# MB1296-LRA_Module.net
KiCad netlist of a schematic drawn in Altium Designer
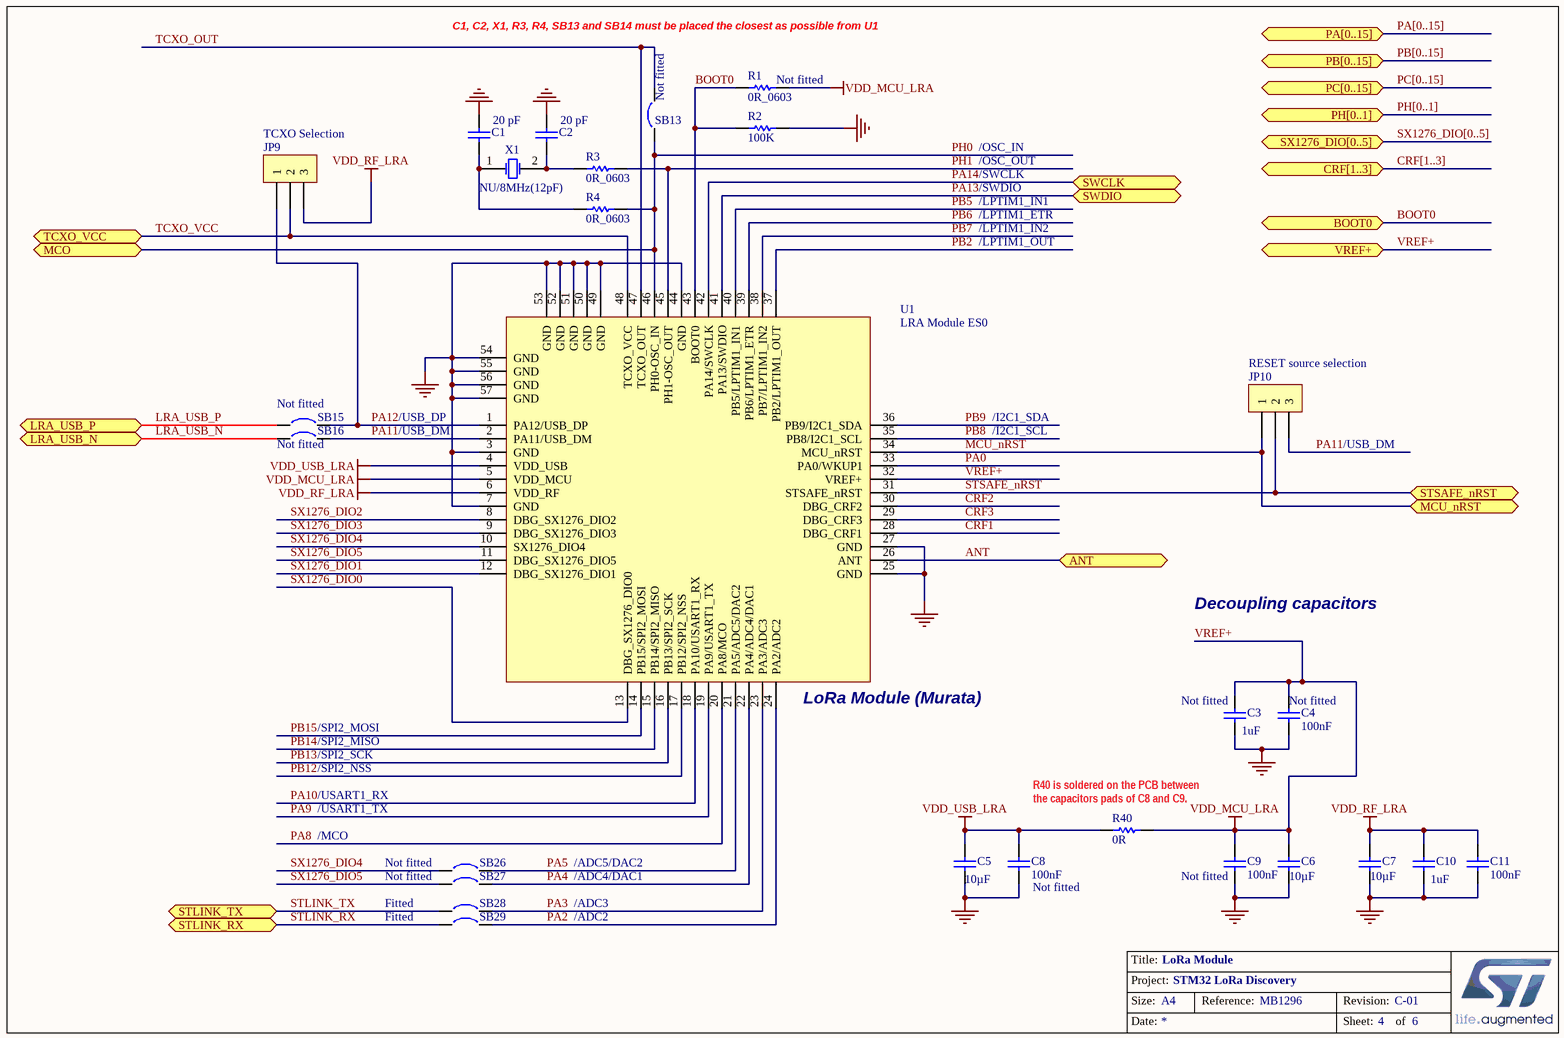
[diagram p0: MB1296-LRA_Module.SchDoc]

(export (version "E")
  (design (tool "Eeschema 10.0.6"))
  (components
    (comp (ref "C1")
      (value "20 pF")
      (footprint "0603C")
      (description "Capacitor 0603")
      (fields (field (name "MANUFACTURER") "YAGEO") (field (name "PROVIDED BY") "Subcon"))
      (libsource (lib "MCD16-033-STM32_LRA_Eval_Board_1") (part "Capacitor_ST"))
    )
    (comp (ref "C2")
      (value "20 pF")
      (footprint "0603C")
      (description "Capacitor 0603")
      (fields (field (name "MANUFACTURER") "YAGEO") (field (name "PROVIDED BY") "Subcon"))
      (libsource (lib "MCD16-033-STM32_LRA_Eval_Board_1") (part "Capacitor_ST"))
    )
    (comp (ref "C3")
      (value "1uF")
      (footprint "0603C")
      (description "0603  X5R 1µF")
      (fields (field (name "MANUFACTURER") "YAGEO") (field (name "PROVIDED BY") "Subcon"))
      (libsource (lib "MCD16-033-STM32_LRA_Eval_Board_1") (part "CAP SMD 0603  X5R 1µF 25V 10%"))
    )
    (comp (ref "C4")
      (value "100nF")
      (footprint "0603C")
      (description "Capacitor 100nF")
      (fields (field (name "MANUFACTURER") "YAGEO") (field (name "PROVIDED BY") "Subcon"))
      (libsource (lib "MCD16-033-STM32_LRA_Eval_Board_1") (part "CAP"))
    )
    (comp (ref "C5")
      (value "10µF")
      (footprint "0603C")
      (description "Capacitor SMD 0805 10000000pF X7R 10V +/-10%")
      (fields (field (name "MANUFACTURER") "Kemet") (field (name "TOLERANCE") "10%"))
      (libsource (lib "Capacitor_0805") (part "CAP_C0805C106K8RACTU"))
    )
    (comp (ref "C6")
      (value "10µF")
      (footprint "0603C")
      (description "Capacitor SMD 0805 10000000pF X7R 10V +/-10%")
      (fields (field (name "MANUFACTURER") "Kemet") (field (name "TOLERANCE") "10%"))
      (libsource (lib "Capacitor_0805") (part "CAP_C0805C106K8RACTU"))
    )
    (comp (ref "C7")
      (value "10µF")
      (footprint "0603C")
      (description "Capacitor SMD 0805 10000000pF X7R 10V +/-10%")
      (fields (field (name "MANUFACTURER") "Kemet") (field (name "TOLERANCE") "10%"))
      (libsource (lib "Capacitor_0805") (part "CAP_C0805C106K8RACTU"))
    )
    (comp (ref "C8")
      (value "100nF")
      (footprint "0603C")
      (description "Capacitor 100nF")
      (fields (field (name "MANUFACTURER") "YAGEO") (field (name "PROVIDED BY") "Subcon"))
      (libsource (lib "MCD16-033-STM32_LRA_Eval_Board_1") (part "CAP"))
    )
    (comp (ref "C9")
      (value "100nF")
      (footprint "0603C")
      (description "Capacitor 100nF")
      (fields (field (name "MANUFACTURER") "YAGEO") (field (name "PROVIDED BY") "Subcon"))
      (libsource (lib "MCD16-033-STM32_LRA_Eval_Board_1") (part "CAP"))
    )
    (comp (ref "C10")
      (value "1uF")
      (footprint "0603C")
      (description "0603  X5R 1µF")
      (fields (field (name "MANUFACTURER") "YAGEO") (field (name "PROVIDED BY") "Subcon"))
      (libsource (lib "MCD16-033-STM32_LRA_Eval_Board_1") (part "CAP SMD 0603  X5R 1µF 25V 10%"))
    )
    (comp (ref "C11")
      (value "100nF")
      (footprint "0603C")
      (description "Capacitor 100nF")
      (fields (field (name "MANUFACTURER") "YAGEO") (field (name "PROVIDED BY") "Subcon"))
      (libsource (lib "MCD16-033-STM32_LRA_Eval_Board_1") (part "CAP"))
    )
    (comp (ref "JP9")
      (value "TCXO Selection")
      (footprint "SIP3")
      (description "Header 3")
      (fields (field (name "MANUFACTURER") "Kontek") (field (name "PROVIDED BY") "Subcon"))
      (libsource (lib "MCD16-033-STM32_LRA_Eval_Board_1") (part "Header 3"))
    )
    (comp (ref "JP10")
      (value "RESET source selection")
      (footprint "SIP3")
      (description "Header 3")
      (fields (field (name "MANUFACTURER") "Kontek") (field (name "PROVIDED BY") "Subcon"))
      (libsource (lib "MCD16-033-STM32_LRA_Eval_Board_1") (part "Header 3"))
    )
    (comp (ref "R1")
      (value "0R_0603")
      (footprint "0603")
      (description "0603 0R 50V 0.1W")
      (fields (field (name "MANUFACTURER") "YAGEO"))
      (libsource (lib "Resistor_0603") (part "RES SMD 0603 0R 50V 0.1W"))
    )
    (comp (ref "R2")
      (value "100K")
      (footprint "0603")
      (description "0603 100K 75V 5% 0.1W")
      (fields (field (name "MANUFACTURER") "YAGEO") (field (name "PROVIDED BY") "Subcon"))
      (libsource (lib "MCD16-033-STM32_LRA_Eval_Board_1") (part "RES SMD 0603 100K 75V 5% 0.1W"))
    )
    (comp (ref "R3")
      (value "0R_0603")
      (footprint "0603")
      (description "0603 0R 50V 0.1W")
      (fields (field (name "MANUFACTURER") "YAGEO"))
      (libsource (lib "Resistor_0603") (part "RES SMD 0603 0R 50V 0.1W"))
    )
    (comp (ref "R4")
      (value "0R_0603")
      (footprint "0603")
      (description "0603 0R 50V 0.1W")
      (fields (field (name "MANUFACTURER") "YAGEO"))
      (libsource (lib "Resistor_0603") (part "RES SMD 0603 0R 50V 0.1W"))
    )
    (comp (ref "R40")
      (value "0R")
      (footprint "0603")
      (description "0603 100K 75V 5% 0.1W")
      (fields (field (name "MANUFACTURER") "YAGEO") (field (name "PROVIDED BY") "Subcon"))
      (libsource (lib "MCD16-033-STM32_LRA_Eval_Board_1") (part "RES SMD 0603 100K 75V 5% 0.1W"))
    )
    (comp (ref "SB13")
      (value "Circuit Breaker")
      (footprint "JP2_SMD")
      (libsource (lib "MCD16-033-STM32_LRA_Eval_Board_1") (part "Circuit Breaker"))
    )
    (comp (ref "SB15")
      (value "Circuit Breaker")
      (footprint "JP2_SMD")
      (libsource (lib "MCD16-033-STM32_LRA_Eval_Board_1") (part "Circuit Breaker"))
    )
    (comp (ref "SB16")
      (value "Circuit Breaker")
      (footprint "JP2_SMD")
      (libsource (lib "MCD16-033-STM32_LRA_Eval_Board_1") (part "Circuit Breaker"))
    )
    (comp (ref "SB26")
      (value "Circuit Breaker")
      (footprint "JP2_SMD")
      (libsource (lib "MCD16-033-STM32_LRA_Eval_Board_1") (part "Circuit Breaker"))
    )
    (comp (ref "SB27")
      (value "Circuit Breaker")
      (footprint "JP2_SMD")
      (libsource (lib "MCD16-033-STM32_LRA_Eval_Board_1") (part "Circuit Breaker"))
    )
    (comp (ref "SB28")
      (value "Circuit Breaker")
      (footprint "JP2_SMD")
      (libsource (lib "MCD16-033-STM32_LRA_Eval_Board_1") (part "Circuit Breaker"))
    )
    (comp (ref "SB29")
      (value "Circuit Breaker")
      (footprint "JP2_SMD")
      (libsource (lib "MCD16-033-STM32_LRA_Eval_Board_1") (part "Circuit Breaker"))
    )
    (comp (ref "U1")
      (value "LRA Module ES0")
      (footprint "Lora Module ES0")
      (fields (field (name "MANUFACTURER") "Murata") (field (name "PROVIDED BY") "Murata"))
      (libsource (lib "Integrated_Circuit") (part "LRA Module ES0"))
    )
    (comp (ref "X1")
      (value "NU/8MHz(12pF)")
      (footprint "CRY_NX3225GD_2P")
      (description "Crystal Oscillator")
      (fields (field (name "MANUFACTURER") "HongKongCrystal") (field (name "PROVIDED BY") "Subcon"))
      (libsource (lib "MB963_1") (part "XTAL"))
    )
  )
  (nets
    (net (code "27") (name "/ANT") (class "Default")
      (node (ref "U1") (pin "26") (pinfunction "ANT_26") (pintype "passive"))
    )
    (net (code "28") (name "/BOOT0") (class "Default")
      (node (ref "R1") (pin "1") (pinfunction "1_1") (pintype "passive"))
      (node (ref "R2") (pin "2") (pinfunction "2_2") (pintype "passive"))
      (node (ref "U1") (pin "43") (pinfunction "BOOT0_43") (pintype "passive"))
    )
    (net (code "29") (name "/CRF1") (class "Default")
      (node (ref "U1") (pin "28") (pinfunction "DBG_CRF1_28") (pintype "passive"))
    )
    (net (code "30") (name "/CRF2") (class "Default")
      (node (ref "U1") (pin "30") (pinfunction "DBG_CRF2_30") (pintype "passive"))
    )
    (net (code "31") (name "/CRF3") (class "Default")
      (node (ref "U1") (pin "29") (pinfunction "DBG_CRF3_29") (pintype "passive"))
    )
    (net (code "33") (name "/LRA_USB_N") (class "Default")
      (node (ref "SB16") (pin "1") (pinfunction "1_1") (pintype "passive"))
    )
    (net (code "34") (name "/LRA_USB_P") (class "Default")
      (node (ref "SB15") (pin "1") (pinfunction "1_1") (pintype "passive"))
    )
    (net (code "35") (name "/MCU_nRST") (class "Default")
      (node (ref "JP10") (pin "1") (pinfunction "1_1") (pintype "passive"))
      (node (ref "U1") (pin "34") (pinfunction "MCU_nRST_34") (pintype "passive"))
    )
    (net (code "36") (name "/PA0") (class "Default")
      (node (ref "U1") (pin "33") (pinfunction "PA0/WKUP1_33") (pintype "passive"))
    )
    (net (code "37") (name "/PA2") (class "Default")
      (node (ref "SB29") (pin "2") (pinfunction "2_2") (pintype "passive"))
      (node (ref "U1") (pin "24") (pinfunction "PA2/ADC2_24") (pintype "passive"))
    )
    (net (code "38") (name "/PA3") (class "Default")
      (node (ref "SB28") (pin "2") (pinfunction "2_2") (pintype "passive"))
      (node (ref "U1") (pin "23") (pinfunction "PA3/ADC3_23") (pintype "passive"))
    )
    (net (code "39") (name "/PA4") (class "Default")
      (node (ref "SB27") (pin "2") (pinfunction "2_2") (pintype "passive"))
      (node (ref "U1") (pin "22") (pinfunction "PA4/ADC4/DAC1_22") (pintype "passive"))
    )
    (net (code "40") (name "/PA5") (class "Default")
      (node (ref "SB26") (pin "2") (pinfunction "2_2") (pintype "passive"))
      (node (ref "U1") (pin "21") (pinfunction "PA5/ADC5/DAC2_21") (pintype "passive"))
    )
    (net (code "41") (name "/PA8") (class "Default")
      (node (ref "U1") (pin "20") (pinfunction "PA8/MCO_20") (pintype "passive"))
    )
    (net (code "42") (name "/PA9") (class "Default")
      (node (ref "U1") (pin "19") (pinfunction "PA9/USART1_TX_19") (pintype "passive"))
    )
    (net (code "43") (name "/PA10") (class "Default")
      (node (ref "U1") (pin "18") (pinfunction "PA10/USART1_RX_18") (pintype "passive"))
    )
    (net (code "44") (name "/PA11") (class "Default")
      (node (ref "JP10") (pin "3") (pinfunction "3_3") (pintype "passive"))
      (node (ref "SB16") (pin "2") (pinfunction "2_2") (pintype "passive"))
      (node (ref "U1") (pin "2") (pinfunction "PA11/USB_DM_2") (pintype "passive"))
    )
    (net (code "45") (name "/PA12") (class "Default")
      (node (ref "JP9") (pin "1") (pinfunction "1_1") (pintype "passive"))
      (node (ref "SB15") (pin "2") (pinfunction "2_2") (pintype "passive"))
      (node (ref "U1") (pin "1") (pinfunction "PA12/USB_DP_1") (pintype "passive"))
    )
    (net (code "46") (name "/PA13") (class "Default")
      (node (ref "U1") (pin "41") (pinfunction "PA13/SWDIO_41") (pintype "passive"))
    )
    (net (code "47") (name "/PA14") (class "Default")
      (node (ref "U1") (pin "42") (pinfunction "PA14/SWCLK_42") (pintype "passive"))
    )
    (net (code "49") (name "/PB2") (class "Default")
      (node (ref "U1") (pin "37") (pinfunction "PB2/LPTIM1_OUT_37") (pintype "passive"))
    )
    (net (code "50") (name "/PB5") (class "Default")
      (node (ref "U1") (pin "40") (pinfunction "PB5/LPTIM1_IN1_40") (pintype "passive"))
    )
    (net (code "51") (name "/PB6") (class "Default")
      (node (ref "U1") (pin "39") (pinfunction "PB6/LPTIM1_ETR_39") (pintype "passive"))
    )
    (net (code "52") (name "/PB7") (class "Default")
      (node (ref "U1") (pin "38") (pinfunction "PB7/LPTIM1_IN2_38") (pintype "passive"))
    )
    (net (code "53") (name "/PB8") (class "Default")
      (node (ref "U1") (pin "35") (pinfunction "PB8/I2C1_SCL_35") (pintype "passive"))
    )
    (net (code "54") (name "/PB9") (class "Default")
      (node (ref "U1") (pin "36") (pinfunction "PB9/I2C1_SDA_36") (pintype "passive"))
    )
    (net (code "55") (name "/PB12") (class "Default")
      (node (ref "U1") (pin "17") (pinfunction "PB12/SPI2_NSS_17") (pintype "passive"))
    )
    (net (code "56") (name "/PB13") (class "Default")
      (node (ref "U1") (pin "16") (pinfunction "PB13/SPI2_SCK_16") (pintype "passive"))
    )
    (net (code "57") (name "/PB14") (class "Default")
      (node (ref "U1") (pin "15") (pinfunction "PB14/SPI2_MISO_15") (pintype "passive"))
    )
    (net (code "58") (name "/PB15") (class "Default")
      (node (ref "U1") (pin "14") (pinfunction "PB15/SPI2_MOSI_14") (pintype "passive"))
    )
    (net (code "61") (name "/PH0") (class "Default")
      (node (ref "R4") (pin "2") (pinfunction "2_2") (pintype "passive"))
      (node (ref "SB13") (pin "1") (pinfunction "1_1") (pintype "passive"))
      (node (ref "U1") (pin "46") (pinfunction "PH0-OSC_IN_46") (pintype "passive"))
    )
    (net (code "62") (name "/PH1") (class "Default")
      (node (ref "R3") (pin "2") (pinfunction "2_2") (pintype "passive"))
      (node (ref "U1") (pin "45") (pinfunction "PH1-OSC_OUT_45") (pintype "passive"))
    )
    (net (code "64") (name "/STLINK_RX") (class "Default")
      (node (ref "SB29") (pin "1") (pinfunction "1_1") (pintype "passive"))
    )
    (net (code "65") (name "/STLINK_TX") (class "Default")
      (node (ref "SB28") (pin "1") (pinfunction "1_1") (pintype "passive"))
    )
    (net (code "66") (name "/STSAFE_nRST") (class "Default")
      (node (ref "JP10") (pin "2") (pinfunction "2_2") (pintype "passive"))
      (node (ref "U1") (pin "31") (pinfunction "STSAFE_nRST_31") (pintype "passive"))
    )
    (net (code "67") (name "/SX1276_DIO0") (class "Default")
      (node (ref "U1") (pin "13") (pinfunction "DBG_SX1276_DIO0_13") (pintype "passive"))
    )
    (net (code "68") (name "/SX1276_DIO1") (class "Default")
      (node (ref "U1") (pin "12") (pinfunction "DBG_SX1276_DIO1_12") (pintype "passive"))
    )
    (net (code "69") (name "/SX1276_DIO2") (class "Default")
      (node (ref "U1") (pin "8") (pinfunction "DBG_SX1276_DIO2_8") (pintype "passive"))
    )
    (net (code "70") (name "/SX1276_DIO3") (class "Default")
      (node (ref "U1") (pin "9") (pinfunction "DBG_SX1276_DIO3_9") (pintype "passive"))
    )
    (net (code "71") (name "/SX1276_DIO4") (class "Default")
      (node (ref "SB26") (pin "1") (pinfunction "1_1") (pintype "passive"))
      (node (ref "U1") (pin "10") (pinfunction "SX1276_DIO4_10") (pintype "passive"))
    )
    (net (code "72") (name "/SX1276_DIO5") (class "Default")
      (node (ref "SB27") (pin "1") (pinfunction "1_1") (pintype "passive"))
      (node (ref "U1") (pin "11") (pinfunction "DBG_SX1276_DIO5_11") (pintype "passive"))
    )
    (net (code "74") (name "/TCXO_OUT") (class "Default")
      (node (ref "SB13") (pin "2") (pinfunction "2_2") (pintype "passive"))
      (node (ref "U1") (pin "47") (pinfunction "TCXO_OUT_47") (pintype "passive"))
    )
    (net (code "75") (name "/TCXO_VCC") (class "Default")
      (node (ref "JP9") (pin "2") (pinfunction "2_2") (pintype "passive"))
      (node (ref "U1") (pin "48") (pinfunction "TCXO_VCC_48") (pintype "passive"))
    )
    (net (code "76") (name "GND") (class "Default")
      (node (ref "C1") (pin "2") (pinfunction "2_2") (pintype "passive"))
      (node (ref "C10") (pin "1") (pinfunction "1_1") (pintype "passive"))
      (node (ref "C11") (pin "1") (pinfunction "1_1") (pintype "passive"))
      (node (ref "C2") (pin "2") (pinfunction "2_2") (pintype "passive"))
      (node (ref "C3") (pin "1") (pinfunction "1_1") (pintype "passive"))
      (node (ref "C4") (pin "1") (pinfunction "1_1") (pintype "passive"))
      (node (ref "C5") (pin "2") (pinfunction "2_2") (pintype "passive"))
      (node (ref "C6") (pin "2") (pinfunction "2_2") (pintype "passive"))
      (node (ref "C7") (pin "2") (pinfunction "2_2") (pintype "passive"))
      (node (ref "C8") (pin "1") (pinfunction "1_1") (pintype "passive"))
      (node (ref "C9") (pin "1") (pinfunction "1_1") (pintype "passive"))
      (node (ref "R2") (pin "1") (pinfunction "1_1") (pintype "passive"))
      (node (ref "U1") (pin "25") (pinfunction "GND_25") (pintype "passive"))
      (node (ref "U1") (pin "27") (pinfunction "GND_27") (pintype "passive"))
      (node (ref "U1") (pin "3") (pinfunction "GND_3") (pintype "passive"))
      (node (ref "U1") (pin "44") (pinfunction "GND_44") (pintype "passive"))
      (node (ref "U1") (pin "49") (pinfunction "GND_49") (pintype "passive"))
      (node (ref "U1") (pin "50") (pinfunction "GND_50") (pintype "passive"))
      (node (ref "U1") (pin "51") (pinfunction "GND_51") (pintype "passive"))
      (node (ref "U1") (pin "52") (pinfunction "GND_52") (pintype "passive"))
      (node (ref "U1") (pin "53") (pinfunction "GND_53") (pintype "passive"))
      (node (ref "U1") (pin "54") (pinfunction "GND_54") (pintype "passive"))
      (node (ref "U1") (pin "55") (pinfunction "GND_55") (pintype "passive"))
      (node (ref "U1") (pin "56") (pinfunction "GND_56") (pintype "passive"))
      (node (ref "U1") (pin "57") (pinfunction "GND_57") (pintype "passive"))
      (node (ref "U1") (pin "7") (pinfunction "GND_7") (pintype "passive"))
    )
    (net (code "77") (name "Net-(X1-OSC1)") (class "Default")
      (node (ref "C1") (pin "1") (pinfunction "1_1") (pintype "passive"))
      (node (ref "R4") (pin "1") (pinfunction "1_1") (pintype "passive"))
      (node (ref "X1") (pin "1") (pinfunction "OSC1_1") (pintype "passive"))
    )
    (net (code "78") (name "Net-(X1-OSC2)") (class "Default")
      (node (ref "C2") (pin "1") (pinfunction "1_1") (pintype "passive"))
      (node (ref "R3") (pin "1") (pinfunction "1_1") (pintype "passive"))
      (node (ref "X1") (pin "2") (pinfunction "OSC2_2") (pintype "passive"))
    )
    (net (code "79") (name "VDD_MCU_LRA") (class "Default")
      (node (ref "C3") (pin "2") (pinfunction "2_2") (pintype "passive"))
      (node (ref "C4") (pin "2") (pinfunction "2_2") (pintype "passive"))
      (node (ref "C6") (pin "1") (pinfunction "1_1") (pintype "passive"))
      (node (ref "C9") (pin "2") (pinfunction "2_2") (pintype "passive"))
      (node (ref "R1") (pin "2") (pinfunction "2_2") (pintype "passive"))
      (node (ref "R40") (pin "1") (pinfunction "1_1") (pintype "passive"))
      (node (ref "U1") (pin "32") (pinfunction "VREF+_32") (pintype "passive"))
      (node (ref "U1") (pin "5") (pinfunction "VDD_MCU_5") (pintype "passive"))
    )
    (net (code "80") (name "VDD_RF_LRA") (class "Default")
      (node (ref "C10") (pin "2") (pinfunction "2_2") (pintype "passive"))
      (node (ref "C11") (pin "2") (pinfunction "2_2") (pintype "passive"))
      (node (ref "C7") (pin "1") (pinfunction "1_1") (pintype "passive"))
      (node (ref "JP9") (pin "3") (pinfunction "3_3") (pintype "passive"))
      (node (ref "U1") (pin "6") (pinfunction "VDD_RF_6") (pintype "passive"))
    )
    (net (code "81") (name "VDD_USB_LRA") (class "Default")
      (node (ref "C5") (pin "1") (pinfunction "1_1") (pintype "passive"))
      (node (ref "C8") (pin "2") (pinfunction "2_2") (pintype "passive"))
      (node (ref "R40") (pin "2") (pinfunction "2_2") (pintype "passive"))
      (node (ref "U1") (pin "4") (pinfunction "VDD_USB_4") (pintype "passive"))
    )
  )
)
